# C8_CORE_ROBOT_M.net
KiCad netlist of a schematic drawn in Altium Designer
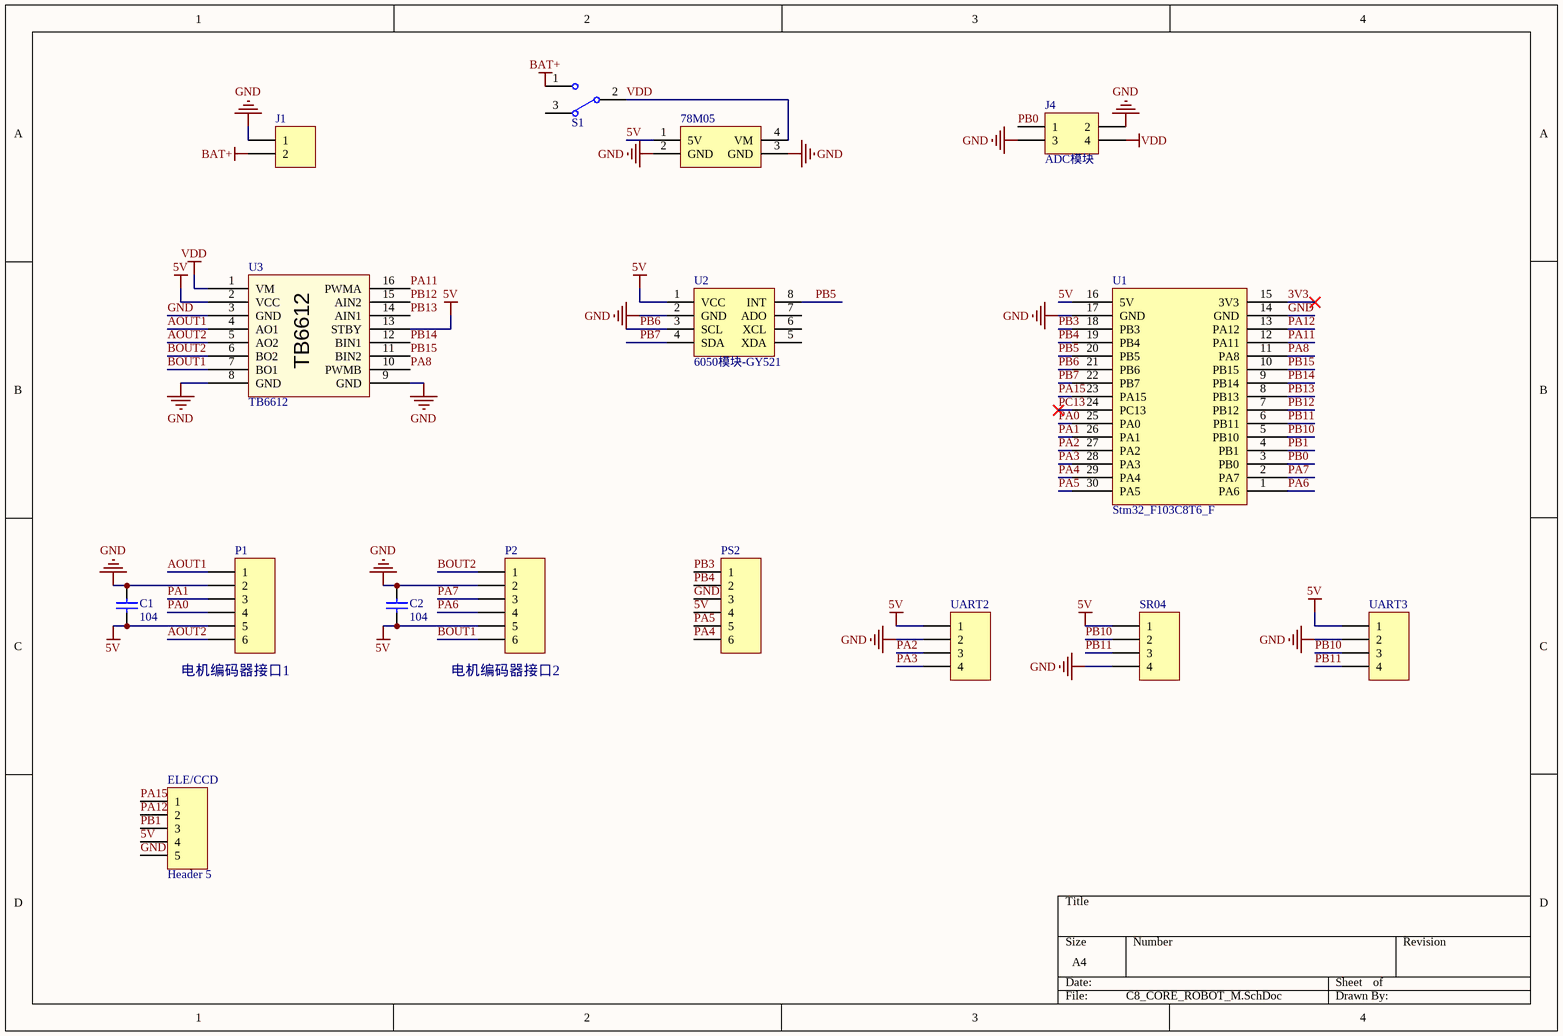
[diagram p0: C8_CORE_ROBOT_M.SchDoc]

(export (version "E")
  (design (tool "Eeschema 10.0.6"))
  (components
    (comp (ref "78M05") (value "78M05") (footprint "MP2259_M0") (libsource (lib "Model") (part "MP2259模块")))
    (comp (ref "C1")
      (value "104")
      (footprint "MLCC5.08-A")
      (description "Capacitor")
      (fields (field (name "PUBLISHER") "Altium Limited"))
      (libsource (lib "Miscellaneous Devices") (part "Cap"))
    )
    (comp (ref "C2")
      (value "104")
      (footprint "MLCC5.08-A")
      (description "Capacitor")
      (fields (field (name "PUBLISHER") "Altium Limited"))
      (libsource (lib "Miscellaneous Devices") (part "Cap"))
    )
    (comp (ref "ELE/CCD")
      (value "Header 5")
      (footprint "XH2.54-LI-5P")
      (description "Header, 5-Pin")
      (fields (field (name "PUBLISHER") "Altium Limited"))
      (libsource (lib "Miscellaneous Connectors") (part "Header 5"))
    )
    (comp (ref "J1")
      (value "Header 2")
      (footprint "XT30-PW-M")
      (description "Header, 2-Pin")
      (fields (field (name "PUBLISHER") "Altium Limited"))
      (libsource (lib "Miscellaneous Connectors") (part "Header 2"))
    )
    (comp (ref "J4")
      (value "ADC模块")
      (footprint "ADC_A0")
      (description "Header, 2-Pin, Dual row")
      (fields (field (name "PUBLISHER") "Altium Limited"))
      (libsource (lib "Miscellaneous Connectors") (part "Header 2X2"))
    )
    (comp (ref "P1")
      (value "Header 6")
      (footprint "XH2.54-WI-6P")
      (description "Header, 6-Pin")
      (fields (field (name "PUBLISHER") "Altium Limited"))
      (libsource (lib "Miscellaneous Connectors") (part "Header 6"))
    )
    (comp (ref "P2")
      (value "Header 6")
      (footprint "XH2.54-WI-6P")
      (description "Header, 6-Pin")
      (fields (field (name "PUBLISHER") "Altium Limited"))
      (libsource (lib "Miscellaneous Connectors") (part "Header 6"))
    )
    (comp (ref "PS2")
      (value "Header 6")
      (footprint "XH2.54-LI-6P")
      (description "Header, 6-Pin")
      (fields (field (name "PUBLISHER") "Altium Limited"))
      (libsource (lib "Miscellaneous Connectors") (part "Header 6"))
    )
    (comp (ref "S1")
      (value "SW-SPDT")
      (footprint "SW")
      (description "SPDT Subminiature Toggle Switch, Right Angle Mounting, Vertical Actuation")
      (fields (field (name "PUBLISHER") "Altium Limited"))
      (libsource (lib "Miscellaneous Devices") (part "SW-SPDT"))
    )
    (comp (ref "SR04")
      (value "Header 4")
      (footprint "HDR1X4")
      (description "Header, 4-Pin")
      (fields (field (name "PUBLISHER") "Altium Limited"))
      (libsource (lib "Miscellaneous Connectors") (part "Header 4"))
    )
    (comp (ref "U1")
      (value "Stm32_F103C8T6_F")
      (footprint "Stm32_F103C8T6_F")
      (libsource (lib "Model") (part "Stm32_F103C8T6_F"))
    )
    (comp (ref "U2")
      (value "6050模块-GY521")
      (footprint "MPU6050_B1")
      (libsource (lib "Model") (part "6050模块-GY521"))
    )
    (comp (ref "U3") (value "TB6612") (footprint "TB6612模块") (libsource (lib "DAYU") (part "DAYU_TB6612")))
    (comp (ref "UART2")
      (value "Header 4")
      (footprint "HDR1X4")
      (description "Header, 4-Pin")
      (fields (field (name "PUBLISHER") "Altium Limited"))
      (libsource (lib "Miscellaneous Connectors") (part "Header 4"))
    )
    (comp (ref "UART3")
      (value "Header 4")
      (footprint "HDR1X4")
      (description "Header, 4-Pin")
      (fields (field (name "PUBLISHER") "Altium Limited"))
      (libsource (lib "Miscellaneous Connectors") (part "Header 4"))
    )
  )
  (nets
    (net (code "1") (name "/3V3") (class "Default")
      (node (ref "U1") (pin "15") (pinfunction "3V3_15") (pintype "passive+no_connect"))
    )
    (net (code "2") (name "/AOUT1") (class "Default")
      (node (ref "P1") (pin "1") (pinfunction "1_1") (pintype "passive"))
      (node (ref "U3") (pin "4") (pinfunction "AO1_4") (pintype "passive"))
    )
    (net (code "3") (name "/AOUT2") (class "Default")
      (node (ref "P1") (pin "6") (pinfunction "6_6") (pintype "passive"))
      (node (ref "U3") (pin "5") (pinfunction "AO2_5") (pintype "passive"))
    )
    (net (code "4") (name "/BOUT1") (class "Default")
      (node (ref "P2") (pin "6") (pinfunction "6_6") (pintype "passive"))
      (node (ref "U3") (pin "7") (pinfunction "BO1_7") (pintype "passive"))
    )
    (net (code "5") (name "/BOUT2") (class "Default")
      (node (ref "P2") (pin "1") (pinfunction "1_1") (pintype "passive"))
      (node (ref "U3") (pin "6") (pinfunction "BO2_6") (pintype "passive"))
    )
    (net (code "6") (name "/PA0") (class "Default")
      (node (ref "P1") (pin "4") (pinfunction "4_4") (pintype "passive"))
      (node (ref "U1") (pin "25") (pinfunction "PA0_25") (pintype "passive"))
    )
    (net (code "7") (name "/PA1") (class "Default")
      (node (ref "P1") (pin "3") (pinfunction "3_3") (pintype "passive"))
      (node (ref "U1") (pin "26") (pinfunction "PA1_26") (pintype "passive"))
    )
    (net (code "8") (name "/PA2") (class "Default")
      (node (ref "U1") (pin "27") (pinfunction "PA2_27") (pintype "passive"))
      (node (ref "UART2") (pin "3") (pinfunction "3_3") (pintype "passive"))
    )
    (net (code "9") (name "/PA3") (class "Default")
      (node (ref "U1") (pin "28") (pinfunction "PA3_28") (pintype "passive"))
      (node (ref "UART2") (pin "4") (pinfunction "4_4") (pintype "passive"))
    )
    (net (code "10") (name "/PA4") (class "Default")
      (node (ref "PS2") (pin "6") (pinfunction "6_6") (pintype "passive"))
      (node (ref "U1") (pin "29") (pinfunction "PA4_29") (pintype "passive"))
    )
    (net (code "11") (name "/PA5") (class "Default")
      (node (ref "PS2") (pin "5") (pinfunction "5_5") (pintype "passive"))
      (node (ref "U1") (pin "30") (pinfunction "PA5_30") (pintype "passive"))
    )
    (net (code "12") (name "/PA6") (class "Default")
      (node (ref "P2") (pin "4") (pinfunction "4_4") (pintype "passive"))
      (node (ref "U1") (pin "1") (pinfunction "PA6_1") (pintype "passive"))
    )
    (net (code "13") (name "/PA7") (class "Default")
      (node (ref "P2") (pin "3") (pinfunction "3_3") (pintype "passive"))
      (node (ref "U1") (pin "2") (pinfunction "PA7_2") (pintype "passive"))
    )
    (net (code "14") (name "/PA8") (class "Default")
      (node (ref "U1") (pin "11") (pinfunction "PA8_11") (pintype "passive"))
      (node (ref "U3") (pin "10") (pinfunction "PWMB_10") (pintype "passive"))
    )
    (net (code "15") (name "/PA11") (class "Default")
      (node (ref "U1") (pin "12") (pinfunction "PA11_12") (pintype "passive"))
      (node (ref "U3") (pin "16") (pinfunction "PWMA_16") (pintype "passive"))
    )
    (net (code "16") (name "/PA12") (class "Default")
      (node (ref "ELE/CCD") (pin "2") (pinfunction "2_2") (pintype "passive"))
      (node (ref "U1") (pin "13") (pinfunction "PA12_13") (pintype "passive"))
    )
    (net (code "17") (name "/PA15") (class "Default")
      (node (ref "ELE/CCD") (pin "1") (pinfunction "1_1") (pintype "passive"))
      (node (ref "U1") (pin "23") (pinfunction "PA15_23") (pintype "passive"))
    )
    (net (code "18") (name "/PB0") (class "Default")
      (node (ref "J4") (pin "1") (pinfunction "1_1") (pintype "passive"))
      (node (ref "U1") (pin "3") (pinfunction "PB0_3") (pintype "passive"))
    )
    (net (code "19") (name "/PB1") (class "Default")
      (node (ref "ELE/CCD") (pin "3") (pinfunction "3_3") (pintype "passive"))
      (node (ref "U1") (pin "4") (pinfunction "PB1_4") (pintype "passive"))
    )
    (net (code "20") (name "/PB3") (class "Default")
      (node (ref "PS2") (pin "1") (pinfunction "1_1") (pintype "passive"))
      (node (ref "U1") (pin "18") (pinfunction "PB3_18") (pintype "passive"))
    )
    (net (code "21") (name "/PB4") (class "Default")
      (node (ref "PS2") (pin "2") (pinfunction "2_2") (pintype "passive"))
      (node (ref "U1") (pin "19") (pinfunction "PB4_19") (pintype "passive"))
    )
    (net (code "22") (name "/PB5") (class "Default")
      (node (ref "U1") (pin "20") (pinfunction "PB5_20") (pintype "passive"))
      (node (ref "U2") (pin "8") (pinfunction "INT_8") (pintype "passive"))
    )
    (net (code "23") (name "/PB6") (class "Default")
      (node (ref "U1") (pin "21") (pinfunction "PB6_21") (pintype "passive"))
      (node (ref "U2") (pin "3") (pinfunction "SCL_3") (pintype "passive"))
    )
    (net (code "24") (name "/PB7") (class "Default")
      (node (ref "U1") (pin "22") (pinfunction "PB7_22") (pintype "passive"))
      (node (ref "U2") (pin "4") (pinfunction "SDA_4") (pintype "passive"))
    )
    (net (code "25") (name "/PB10") (class "Default")
      (node (ref "SR04") (pin "2") (pinfunction "2_2") (pintype "passive"))
      (node (ref "U1") (pin "5") (pinfunction "PB10_5") (pintype "passive"))
      (node (ref "UART3") (pin "3") (pinfunction "3_3") (pintype "passive"))
    )
    (net (code "26") (name "/PB11") (class "Default")
      (node (ref "SR04") (pin "3") (pinfunction "3_3") (pintype "passive"))
      (node (ref "U1") (pin "6") (pinfunction "PB11_6") (pintype "passive"))
      (node (ref "UART3") (pin "4") (pinfunction "4_4") (pintype "passive"))
    )
    (net (code "27") (name "/PB12") (class "Default")
      (node (ref "U1") (pin "7") (pinfunction "PB12_7") (pintype "passive"))
      (node (ref "U3") (pin "15") (pinfunction "AIN2_15") (pintype "passive"))
    )
    (net (code "28") (name "/PB13") (class "Default")
      (node (ref "U1") (pin "8") (pinfunction "PB13_8") (pintype "passive"))
      (node (ref "U3") (pin "14") (pinfunction "AIN1_14") (pintype "passive"))
    )
    (net (code "29") (name "/PB14") (class "Default")
      (node (ref "U1") (pin "9") (pinfunction "PB14_9") (pintype "passive"))
      (node (ref "U3") (pin "12") (pinfunction "BIN1_12") (pintype "passive"))
    )
    (net (code "30") (name "/PB15") (class "Default")
      (node (ref "U1") (pin "10") (pinfunction "PB15_10") (pintype "passive"))
      (node (ref "U3") (pin "11") (pinfunction "BIN2_11") (pintype "passive"))
    )
    (net (code "31") (name "/PC13") (class "Default")
      (node (ref "U1") (pin "24") (pinfunction "PC13_24") (pintype "passive+no_connect"))
    )
    (net (code "32") (name "5V") (class "Default")
      (node (ref "78M05") (pin "1") (pinfunction "5V_1") (pintype "passive"))
      (node (ref "C1") (pin "1") (pinfunction "1_1") (pintype "passive"))
      (node (ref "C2") (pin "1") (pinfunction "1_1") (pintype "passive"))
      (node (ref "ELE/CCD") (pin "4") (pinfunction "4_4") (pintype "passive"))
      (node (ref "P1") (pin "5") (pinfunction "5_5") (pintype "passive"))
      (node (ref "P2") (pin "5") (pinfunction "5_5") (pintype "passive"))
      (node (ref "PS2") (pin "4") (pinfunction "4_4") (pintype "passive"))
      (node (ref "SR04") (pin "1") (pinfunction "1_1") (pintype "passive"))
      (node (ref "U1") (pin "16") (pinfunction "5V_16") (pintype "passive"))
      (node (ref "U2") (pin "1") (pinfunction "VCC_1") (pintype "passive"))
      (node (ref "U3") (pin "13") (pinfunction "STBY_13") (pintype "passive"))
      (node (ref "U3") (pin "2") (pinfunction "VCC_2") (pintype "passive"))
      (node (ref "UART2") (pin "1") (pinfunction "1_1") (pintype "passive"))
      (node (ref "UART3") (pin "1") (pinfunction "1_1") (pintype "passive"))
    )
    (net (code "33") (name "BAT+") (class "Default")
      (node (ref "J1") (pin "2") (pinfunction "2_2") (pintype "passive"))
      (node (ref "S1") (pin "1") (pinfunction "1_1") (pintype "passive"))
    )
    (net (code "34") (name "GND") (class "Default")
      (node (ref "78M05") (pin "2") (pinfunction "GND_2") (pintype "passive"))
      (node (ref "78M05") (pin "3") (pinfunction "GND_3") (pintype "passive"))
      (node (ref "C1") (pin "2") (pinfunction "2_2") (pintype "passive"))
      (node (ref "C2") (pin "2") (pinfunction "2_2") (pintype "passive"))
      (node (ref "ELE/CCD") (pin "5") (pinfunction "5_5") (pintype "passive"))
      (node (ref "J1") (pin "1") (pinfunction "1_1") (pintype "passive"))
      (node (ref "J4") (pin "2") (pinfunction "2_2") (pintype "passive"))
      (node (ref "J4") (pin "3") (pinfunction "3_3") (pintype "passive"))
      (node (ref "P1") (pin "2") (pinfunction "2_2") (pintype "passive"))
      (node (ref "P2") (pin "2") (pinfunction "2_2") (pintype "passive"))
      (node (ref "PS2") (pin "3") (pinfunction "3_3") (pintype "passive"))
      (node (ref "SR04") (pin "4") (pinfunction "4_4") (pintype "passive"))
      (node (ref "U1") (pin "14") (pinfunction "GND_14") (pintype "passive"))
      (node (ref "U1") (pin "17") (pinfunction "GND_17") (pintype "passive"))
      (node (ref "U2") (pin "2") (pinfunction "GND_2") (pintype "passive"))
      (node (ref "U3") (pin "3") (pinfunction "GND_3") (pintype "passive"))
      (node (ref "U3") (pin "8") (pinfunction "GND_8") (pintype "passive"))
      (node (ref "U3") (pin "9") (pinfunction "GND_9") (pintype "passive"))
      (node (ref "UART2") (pin "2") (pinfunction "2_2") (pintype "passive"))
      (node (ref "UART3") (pin "2") (pinfunction "2_2") (pintype "passive"))
    )
    (net (code "35") (name "VDD") (class "Default")
      (node (ref "78M05") (pin "4") (pinfunction "VM_4") (pintype "passive"))
      (node (ref "J4") (pin "4") (pinfunction "4_4") (pintype "passive"))
      (node (ref "S1") (pin "2") (pinfunction "2_2") (pintype "passive"))
      (node (ref "U3") (pin "1") (pinfunction "VM_1") (pintype "passive"))
    )
    (net (code "36") (name "unconnected-(S1-Pad3)") (class "Default")
      (node (ref "S1") (pin "3") (pinfunction "3_3") (pintype "passive"))
    )
    (net (code "37") (name "unconnected-(U2-ADO-Pad7)") (class "Default")
      (node (ref "U2") (pin "7") (pinfunction "ADO_7") (pintype "passive"))
    )
    (net (code "38") (name "unconnected-(U2-XCL-Pad6)") (class "Default")
      (node (ref "U2") (pin "6") (pinfunction "XCL_6") (pintype "passive"))
    )
    (net (code "39") (name "unconnected-(U2-XDA-Pad5)") (class "Default")
      (node (ref "U2") (pin "5") (pinfunction "XDA_5") (pintype "passive"))
    )
  )
)
